# NG2093_USB.net
KiCad netlist of a schematic drawn in Altium Designer
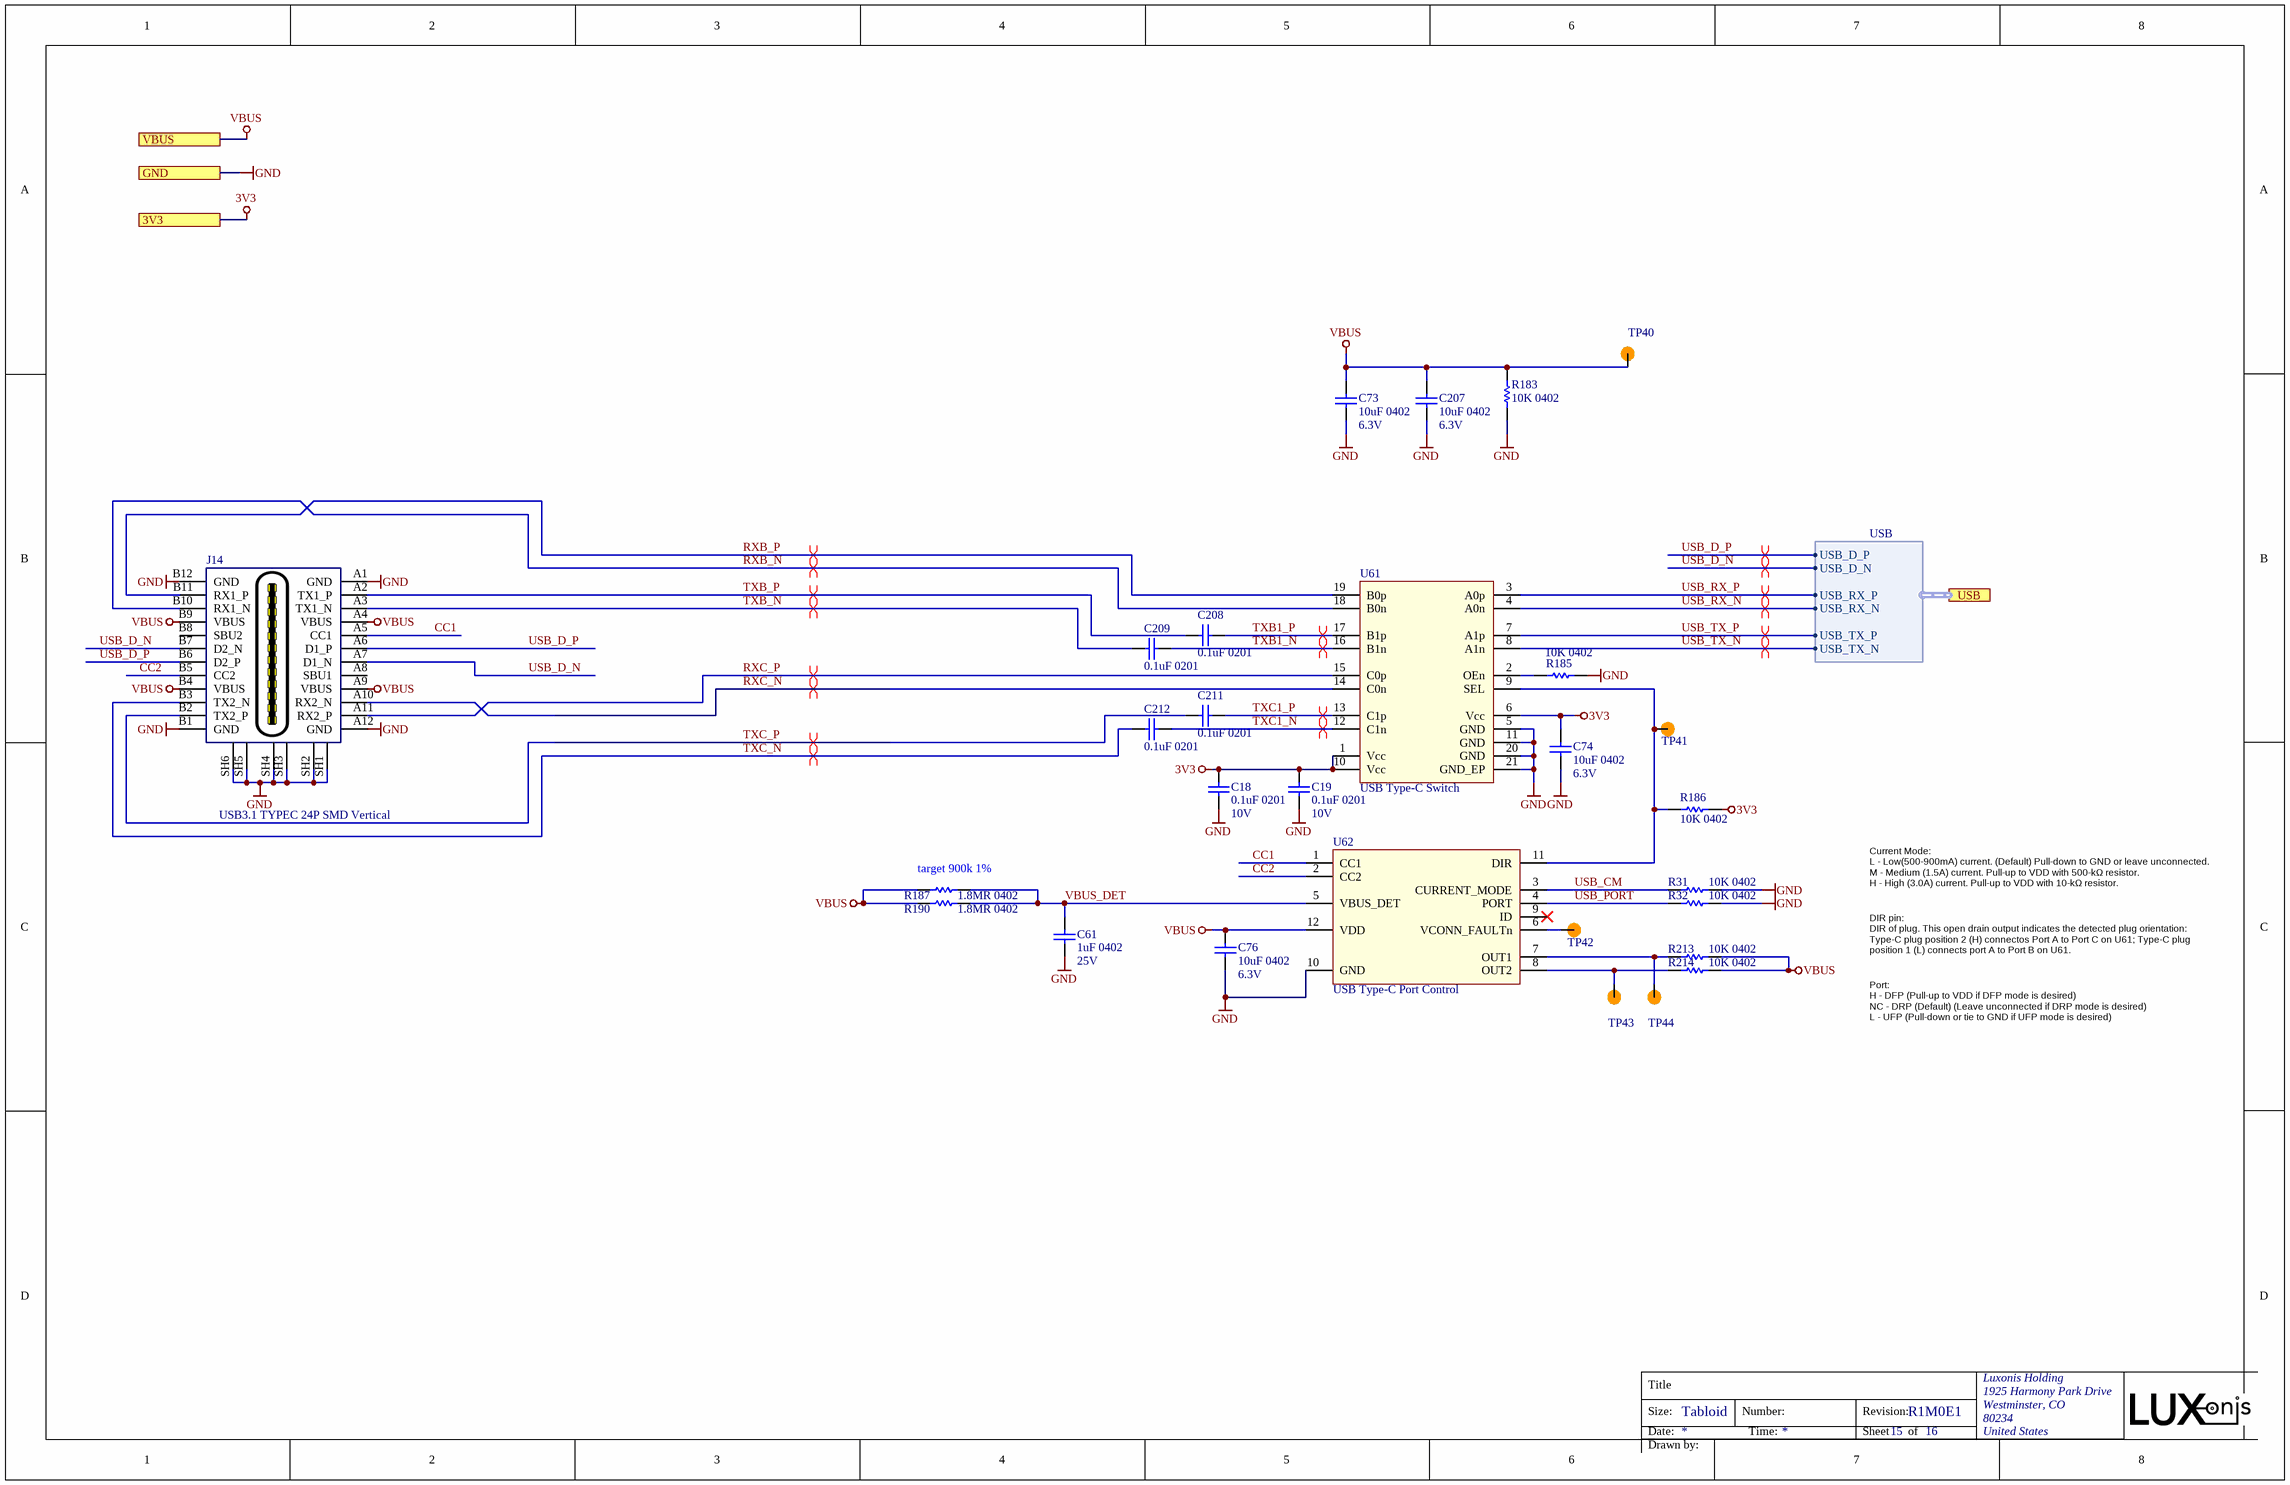
[diagram p0: NG2093_USB.SchDoc]

(export (version "E")
  (design (tool "Eeschema 10.0.6"))
  (components
    (comp (ref "C18")
      (value "0.1uF 0201")
      (footprint "CAP_Altium_Vault_Generic:CAPC0201(0603)33_L")
      (description "CAP CER 0.1UF 10V X5R 0201")
      (fields (field (name "TOLERANCE") "10%") (field (name "VOLTAGE") "10V"))
      (libsource (lib "LuxonisMaster") (part "GRM033R61A104KE15D"))
    )
    (comp (ref "C19")
      (value "0.1uF 0201")
      (footprint "CAP_Altium_Vault_Generic:CAPC0201(0603)33_L")
      (description "CAP CER 0.1UF 10V X5R 0201")
      (fields (field (name "TOLERANCE") "10%") (field (name "VOLTAGE") "10V"))
      (libsource (lib "LuxonisMaster") (part "GRM033R61A104KE15D"))
    )
    (comp (ref "C61")
      (value "1uF 0402")
      (footprint "CAP_Altium_Vault_Generic:CAPC0402(1005)70_N")
      (description "CAP CER 1UF 25V X5R 0402 10%")
      (fields
        (field (name "TOLERANCE") "10%")
        (field (name "VOLTAGE") "25V")
        (field (name "VOLTAGE RATING") "25V")
      )
      (libsource (lib "LuxonisMaster") (part "GRM155R61E105KA12D"))
    )
    (comp (ref "C73")
      (value "10uF 0402")
      (footprint "CAP_Altium_Vault_Generic:CAPC0402(1005)70_N")
      (description "CAP CER 10UF 6.3V X5R 0402 20%")
      (fields (field (name "TOLERANCE") "20%") (field (name "VOLTAGE RATING") "6.3V"))
      (libsource (lib "LuxonisMaster") (part "GRM155R60J106ME15D"))
    )
    (comp (ref "C74")
      (value "10uF 0402")
      (footprint "CAP_Altium_Vault_Generic:CAPC0402(1005)70_N")
      (description "CAP CER 10UF 6.3V X5R 0402 20%")
      (fields (field (name "TOLERANCE") "20%") (field (name "VOLTAGE RATING") "6.3V"))
      (libsource (lib "LuxonisMaster") (part "GRM155R60J106ME15D"))
    )
    (comp (ref "C76")
      (value "10uF 0402")
      (footprint "CAP_Altium_Vault_Generic:CAPC0402(1005)70_N")
      (description "CAP CER 10UF 6.3V X5R 0402 20%")
      (fields (field (name "TOLERANCE") "20%") (field (name "VOLTAGE RATING") "6.3V"))
      (libsource (lib "LuxonisMaster") (part "GRM155R60J106ME15D"))
    )
    (comp (ref "C207")
      (value "10uF 0402")
      (footprint "CAP_Altium_Vault_Generic:CAPC0402(1005)70_N")
      (description "CAP CER 10UF 6.3V X5R 0402 20%")
      (fields (field (name "TOLERANCE") "20%") (field (name "VOLTAGE RATING") "6.3V"))
      (libsource (lib "LuxonisMaster") (part "GRM155R60J106ME15D"))
    )
    (comp (ref "C208")
      (value "0.1uF 0201")
      (footprint "CAP_Altium_Vault_Generic:CAPC0201(0603)33_L")
      (description "CAP CER 0.1UF 10V X5R 0201")
      (fields (field (name "TOLERANCE") "10%") (field (name "VOLTAGE") "10V"))
      (libsource (lib "LuxonisMaster") (part "GRM033R61A104KE15D"))
    )
    (comp (ref "C209")
      (value "0.1uF 0201")
      (footprint "CAP_Altium_Vault_Generic:CAPC0201(0603)33_L")
      (description "CAP CER 0.1UF 10V X5R 0201")
      (fields (field (name "TOLERANCE") "10%") (field (name "VOLTAGE") "10V"))
      (libsource (lib "LuxonisMaster") (part "GRM033R61A104KE15D"))
    )
    (comp (ref "C211")
      (value "0.1uF 0201")
      (footprint "CAP_Altium_Vault_Generic:CAPC0201(0603)33_L")
      (description "CAP CER 0.1UF 10V X5R 0201")
      (fields (field (name "TOLERANCE") "10%") (field (name "VOLTAGE") "10V"))
      (libsource (lib "LuxonisMaster") (part "GRM033R61A104KE15D"))
    )
    (comp (ref "C212")
      (value "0.1uF 0201")
      (footprint "CAP_Altium_Vault_Generic:CAPC0201(0603)33_L")
      (description "CAP CER 0.1UF 10V X5R 0201")
      (fields (field (name "TOLERANCE") "10%") (field (name "VOLTAGE") "10V"))
      (libsource (lib "LuxonisMaster") (part "GRM033R61A104KE15D"))
    )
    (comp (ref "J14")
      (value "USB3.1 TYPEC 24P SMD Vertical")
      (footprint "SJ2088POE:CX80B1-24P")
      (description "CONN RCPT USB3.1 TYPEC 24POS SMD Vertical")
      (libsource (lib "SJ2088POE") (part "CX80B1-24P"))
    )
    (comp (ref "R31")
      (value "10K 0402")
      (footprint "RESC0402(1005)_N")
      (fields (field (name "TOLERANCE") "1%"))
      (libsource (lib "LuxonisMaster") (part "RC0402FR-1310KL"))
    )
    (comp (ref "R32")
      (value "10K 0402")
      (footprint "RESC0402(1005)_N")
      (fields (field (name "TOLERANCE") "1%"))
      (libsource (lib "LuxonisMaster") (part "RC0402FR-1310KL"))
    )
    (comp (ref "R183")
      (value "10K 0402")
      (footprint "RESC0402(1005)_N")
      (fields (field (name "TOLERANCE") "1%"))
      (libsource (lib "LuxonisMaster") (part "RC0402FR-1310KL"))
    )
    (comp (ref "R185")
      (value "10K 0402")
      (footprint "RESC0402(1005)_N")
      (fields (field (name "TOLERANCE") "1%"))
      (libsource (lib "LuxonisMaster") (part "RC0402FR-1310KL"))
    )
    (comp (ref "R186")
      (value "10K 0402")
      (footprint "RESC0402(1005)_N")
      (fields (field (name "TOLERANCE") "1%"))
      (libsource (lib "LuxonisMaster") (part "RC0402FR-1310KL"))
    )
    (comp (ref "R187")
      (value "1.8MR 0402")
      (footprint "RESC0402(1005)_N")
      (description "RES SMD 1.8M OHM 1% 1/16W 0402")
      (fields (field (name "TOLERANCE") "1%"))
      (libsource (lib "LuxonisMaster") (part "CRCW04021M80FKED"))
    )
    (comp (ref "R190")
      (value "1.8MR 0402")
      (footprint "RESC0402(1005)_N")
      (description "RES SMD 1.8M OHM 1% 1/16W 0402")
      (fields (field (name "TOLERANCE") "1%"))
      (libsource (lib "LuxonisMaster") (part "CRCW04021M80FKED"))
    )
    (comp (ref "R213")
      (value "10K 0402")
      (footprint "RESC0402(1005)_N")
      (fields (field (name "TOLERANCE") "1%"))
      (libsource (lib "LuxonisMaster") (part "RC0402FR-1310KL"))
    )
    (comp (ref "R214")
      (value "10K 0402")
      (footprint "RESC0402(1005)_N")
      (fields (field (name "TOLERANCE") "1%"))
      (libsource (lib "LuxonisMaster") (part "RC0402FR-1310KL"))
    )
    (comp (ref "TP40")
      (value "TP100_200_NS")
      (footprint "TP100_200_NS")
      (libsource (lib "LuxonisMaster") (part "TEST_POINT"))
    )
    (comp (ref "TP41")
      (value "TP100_200_NS")
      (footprint "TP100_200_NS")
      (libsource (lib "LuxonisMaster") (part "TEST_POINT"))
    )
    (comp (ref "TP42")
      (value "TP100_200_NS")
      (footprint "TP100_200_NS")
      (libsource (lib "LuxonisMaster") (part "TEST_POINT"))
    )
    (comp (ref "TP43")
      (value "TP100_200_NS")
      (footprint "TP100_200_NS")
      (libsource (lib "LuxonisMaster") (part "TEST_POINT"))
    )
    (comp (ref "TP44")
      (value "TP100_200_NS")
      (footprint "TP100_200_NS")
      (libsource (lib "LuxonisMaster") (part "TEST_POINT"))
    )
    (comp (ref "U61")
      (value "USB Type-C Switch")
      (footprint "CBTL02043A")
      (libsource (lib "LuxonisMaster") (part "CBTL02043A"))
    )
    (comp (ref "U62")
      (value "USB Type-C Port Control")
      (footprint "LuxonisMaster:TUSB321RWBR")
      (description "IC USB PORT CONTROL TYPE-C 12X2Q")
      (libsource (lib "LuxonisMaster") (part "TUSB321RWBR"))
    )
  )
  (nets
    (net (code "2") (name "/CC1") (class "Default")
      (node (ref "J14") (pin "A5") (pinfunction "CC1_A5") (pintype "passive"))
      (node (ref "U62") (pin "1") (pinfunction "CC1_1") (pintype "passive"))
    )
    (net (code "3") (name "/CC2") (class "Default")
      (node (ref "J14") (pin "B5") (pinfunction "CC2_B5") (pintype "passive"))
      (node (ref "U62") (pin "2") (pinfunction "CC2_2") (pintype "passive"))
    )
    (net (code "4") (name "/RXB_N") (class "Default")
      (node (ref "J14") (pin "B10") (pinfunction "RX1_N_B10") (pintype "passive"))
      (node (ref "U61") (pin "18") (pinfunction "B0n_18") (pintype "passive"))
    )
    (net (code "5") (name "/RXB_P") (class "Default")
      (node (ref "J14") (pin "B11") (pinfunction "RX1_P_B11") (pintype "passive"))
      (node (ref "U61") (pin "19") (pinfunction "B0p_19") (pintype "passive"))
    )
    (net (code "6") (name "/RXC_N") (class "Default")
      (node (ref "J14") (pin "A10") (pinfunction "RX2_N_A10") (pintype "passive"))
      (node (ref "U61") (pin "14") (pinfunction "C0n_14") (pintype "passive"))
    )
    (net (code "7") (name "/RXC_P") (class "Default")
      (node (ref "J14") (pin "A11") (pinfunction "RX2_P_A11") (pintype "passive"))
      (node (ref "U61") (pin "15") (pinfunction "C0p_15") (pintype "passive"))
    )
    (net (code "8") (name "/TXB1_N") (class "Default")
      (node (ref "C209") (pin "2") (pinfunction "2_2") (pintype "passive"))
      (node (ref "U61") (pin "16") (pinfunction "B1n_16") (pintype "passive"))
    )
    (net (code "9") (name "/TXB1_P") (class "Default")
      (node (ref "C208") (pin "2") (pinfunction "2_2") (pintype "passive"))
      (node (ref "U61") (pin "17") (pinfunction "B1p_17") (pintype "passive"))
    )
    (net (code "10") (name "/TXB_N") (class "Default")
      (node (ref "C209") (pin "1") (pinfunction "1_1") (pintype "passive"))
      (node (ref "J14") (pin "A3") (pinfunction "TX1_N_A3") (pintype "passive"))
    )
    (net (code "11") (name "/TXB_P") (class "Default")
      (node (ref "C208") (pin "1") (pinfunction "1_1") (pintype "passive"))
      (node (ref "J14") (pin "A2") (pinfunction "TX1_P_A2") (pintype "passive"))
    )
    (net (code "12") (name "/TXC1_N") (class "Default")
      (node (ref "C212") (pin "2") (pinfunction "2_2") (pintype "passive"))
      (node (ref "U61") (pin "12") (pinfunction "C1n_12") (pintype "passive"))
    )
    (net (code "13") (name "/TXC1_P") (class "Default")
      (node (ref "C211") (pin "2") (pinfunction "2_2") (pintype "passive"))
      (node (ref "U61") (pin "13") (pinfunction "C1p_13") (pintype "passive"))
    )
    (net (code "14") (name "/TXC_N") (class "Default")
      (node (ref "C212") (pin "1") (pinfunction "1_1") (pintype "passive"))
      (node (ref "J14") (pin "B3") (pinfunction "TX2_N_B3") (pintype "passive"))
    )
    (net (code "15") (name "/TXC_P") (class "Default")
      (node (ref "C211") (pin "1") (pinfunction "1_1") (pintype "passive"))
      (node (ref "J14") (pin "B2") (pinfunction "TX2_P_B2") (pintype "passive"))
    )
    (net (code "16") (name "/USB_CM") (class "Default")
      (node (ref "R31") (pin "1") (pinfunction "1_1") (pintype "passive"))
      (node (ref "U62") (pin "3") (pinfunction "CURRENT_MODE_3") (pintype "passive"))
    )
    (net (code "17") (name "/USB_D_N") (class "Default")
      (node (ref "J14") (pin "A7") (pinfunction "D1_N_A7") (pintype "passive"))
      (node (ref "J14") (pin "B7") (pinfunction "D2_N_B7") (pintype "passive"))
    )
    (net (code "18") (name "/USB_D_P") (class "Default")
      (node (ref "J14") (pin "A6") (pinfunction "D1_P_A6") (pintype "passive"))
      (node (ref "J14") (pin "B6") (pinfunction "D2_P_B6") (pintype "passive"))
    )
    (net (code "19") (name "/USB_PORT") (class "Default")
      (node (ref "R32") (pin "1") (pinfunction "1_1") (pintype "passive"))
      (node (ref "U62") (pin "4") (pinfunction "PORT_4") (pintype "passive"))
    )
    (net (code "20") (name "/USB_RX_N") (class "Default")
      (node (ref "U61") (pin "4") (pinfunction "A0n_4") (pintype "passive"))
    )
    (net (code "21") (name "/USB_RX_P") (class "Default")
      (node (ref "U61") (pin "3") (pinfunction "A0p_3") (pintype "passive"))
    )
    (net (code "22") (name "/USB_TX_N") (class "Default")
      (node (ref "U61") (pin "8") (pinfunction "A1n_8") (pintype "passive"))
    )
    (net (code "23") (name "/USB_TX_P") (class "Default")
      (node (ref "U61") (pin "7") (pinfunction "A1p_7") (pintype "passive"))
    )
    (net (code "24") (name "/VBUS_DET") (class "Default")
      (node (ref "C61") (pin "2") (pinfunction "2_2") (pintype "passive"))
      (node (ref "R187") (pin "2") (pinfunction "2_2") (pintype "passive"))
      (node (ref "R190") (pin "2") (pinfunction "2_2") (pintype "passive"))
      (node (ref "U62") (pin "5") (pinfunction "VBUS_DET_5") (pintype "passive"))
    )
    (net (code "26") (name "3V3") (class "Default")
      (node (ref "C18") (pin "2") (pinfunction "2_2") (pintype "passive"))
      (node (ref "C19") (pin "2") (pinfunction "2_2") (pintype "passive"))
      (node (ref "C74") (pin "2") (pinfunction "2_2") (pintype "passive"))
      (node (ref "R186") (pin "2") (pinfunction "2_2") (pintype "passive"))
      (node (ref "U61") (pin "1") (pinfunction "Vcc_1") (pintype "passive"))
      (node (ref "U61") (pin "10") (pinfunction "Vcc_10") (pintype "passive"))
      (node (ref "U61") (pin "6") (pinfunction "Vcc_6") (pintype "passive"))
    )
    (net (code "27") (name "GND") (class "Default")
      (node (ref "C18") (pin "1") (pinfunction "1_1") (pintype "passive"))
      (node (ref "C19") (pin "1") (pinfunction "1_1") (pintype "passive"))
      (node (ref "C207") (pin "1") (pinfunction "1_1") (pintype "passive"))
      (node (ref "C61") (pin "1") (pinfunction "1_1") (pintype "passive"))
      (node (ref "C73") (pin "1") (pinfunction "1_1") (pintype "passive"))
      (node (ref "C74") (pin "1") (pinfunction "1_1") (pintype "passive"))
      (node (ref "C76") (pin "1") (pinfunction "1_1") (pintype "passive"))
      (node (ref "J14") (pin "A1") (pinfunction "GND_A1") (pintype "passive"))
      (node (ref "J14") (pin "A12") (pinfunction "GND_A12") (pintype "passive"))
      (node (ref "J14") (pin "B1") (pinfunction "GND_B1") (pintype "passive"))
      (node (ref "J14") (pin "B12") (pinfunction "GND_B12") (pintype "passive"))
      (node (ref "J14") (pin "SH1") (pinfunction "SH_SH1") (pintype "passive"))
      (node (ref "J14") (pin "SH2") (pinfunction "SH_SH2") (pintype "passive"))
      (node (ref "J14") (pin "SH3") (pinfunction "SH_SH3") (pintype "passive"))
      (node (ref "J14") (pin "SH4") (pinfunction "SH_SH4") (pintype "passive"))
      (node (ref "J14") (pin "SH5") (pinfunction "SH_SH5") (pintype "passive"))
      (node (ref "J14") (pin "SH6") (pinfunction "SH_SH6") (pintype "passive"))
      (node (ref "R183") (pin "1") (pinfunction "1_1") (pintype "passive"))
      (node (ref "R185") (pin "2") (pinfunction "2_2") (pintype "passive"))
      (node (ref "R31") (pin "2") (pinfunction "2_2") (pintype "passive"))
      (node (ref "R32") (pin "2") (pinfunction "2_2") (pintype "passive"))
      (node (ref "U61") (pin "11") (pinfunction "GND_11") (pintype "passive"))
      (node (ref "U61") (pin "20") (pinfunction "GND_20") (pintype "passive"))
      (node (ref "U61") (pin "21") (pinfunction "GND_EP_21") (pintype "passive"))
      (node (ref "U61") (pin "5") (pinfunction "GND_5") (pintype "passive"))
      (node (ref "U62") (pin "10") (pinfunction "GND_10") (pintype "passive"))
    )
    (net (code "28") (name "Net-(U61-OEn)") (class "Default")
      (node (ref "R185") (pin "1") (pinfunction "1_1") (pintype "passive"))
      (node (ref "U61") (pin "2") (pinfunction "OEn_2") (pintype "passive"))
    )
    (net (code "29") (name "Net-(U61-SEL)") (class "Default")
      (node (ref "R186") (pin "1") (pinfunction "1_1") (pintype "passive"))
      (node (ref "TP41") (pin "1") (pintype "passive"))
      (node (ref "U61") (pin "9") (pinfunction "SEL_9") (pintype "passive"))
      (node (ref "U62") (pin "11") (pinfunction "DIR_11") (pintype "passive"))
    )
    (net (code "30") (name "Net-(U62-OUT1)") (class "Default")
      (node (ref "R213") (pin "1") (pinfunction "1_1") (pintype "passive"))
      (node (ref "TP44") (pin "1") (pintype "passive"))
      (node (ref "U62") (pin "7") (pinfunction "OUT1_7") (pintype "passive"))
    )
    (net (code "31") (name "Net-(U62-OUT2)") (class "Default")
      (node (ref "R214") (pin "1") (pinfunction "1_1") (pintype "passive"))
      (node (ref "TP43") (pin "1") (pintype "passive"))
      (node (ref "U62") (pin "8") (pinfunction "OUT2_8") (pintype "passive"))
    )
    (net (code "32") (name "Net-(U62-VCONN_FAULTn)") (class "Default")
      (node (ref "TP42") (pin "1") (pintype "passive"))
      (node (ref "U62") (pin "6") (pinfunction "VCONN_FAULTn_6") (pintype "passive"))
    )
    (net (code "33") (name "VBUS") (class "Default")
      (node (ref "C207") (pin "2") (pinfunction "2_2") (pintype "passive"))
      (node (ref "C73") (pin "2") (pinfunction "2_2") (pintype "passive"))
      (node (ref "C76") (pin "2") (pinfunction "2_2") (pintype "passive"))
      (node (ref "J14") (pin "A4") (pinfunction "VBUS_A4") (pintype "passive"))
      (node (ref "J14") (pin "A9") (pinfunction "VBUS_A9") (pintype "passive"))
      (node (ref "J14") (pin "B4") (pinfunction "VBUS_B4") (pintype "passive"))
      (node (ref "J14") (pin "B9") (pinfunction "VBUS_B9") (pintype "passive"))
      (node (ref "R183") (pin "2") (pinfunction "2_2") (pintype "passive"))
      (node (ref "R187") (pin "1") (pinfunction "1_1") (pintype "passive"))
      (node (ref "R190") (pin "1") (pinfunction "1_1") (pintype "passive"))
      (node (ref "R213") (pin "2") (pinfunction "2_2") (pintype "passive"))
      (node (ref "R214") (pin "2") (pinfunction "2_2") (pintype "passive"))
      (node (ref "TP40") (pin "1") (pintype "passive"))
      (node (ref "U62") (pin "12") (pinfunction "VDD_12") (pintype "passive"))
    )
    (net (code "34") (name "unconnected-(J14-SBU1-PadA8)") (class "Default")
      (node (ref "J14") (pin "A8") (pinfunction "SBU1_A8") (pintype "passive"))
    )
    (net (code "35") (name "unconnected-(J14-SBU2-PadB8)") (class "Default")
      (node (ref "J14") (pin "B8") (pinfunction "SBU2_B8") (pintype "passive"))
    )
    (net (code "36") (name "unconnected-(U62-ID-Pad9)") (class "Default")
      (node (ref "U62") (pin "9") (pinfunction "ID_9") (pintype "passive+no_connect"))
    )
  )
)
